# Arduino-UNO-SMD-Rev3e.net
KiCad netlist of a schematic drawn in EAGLE
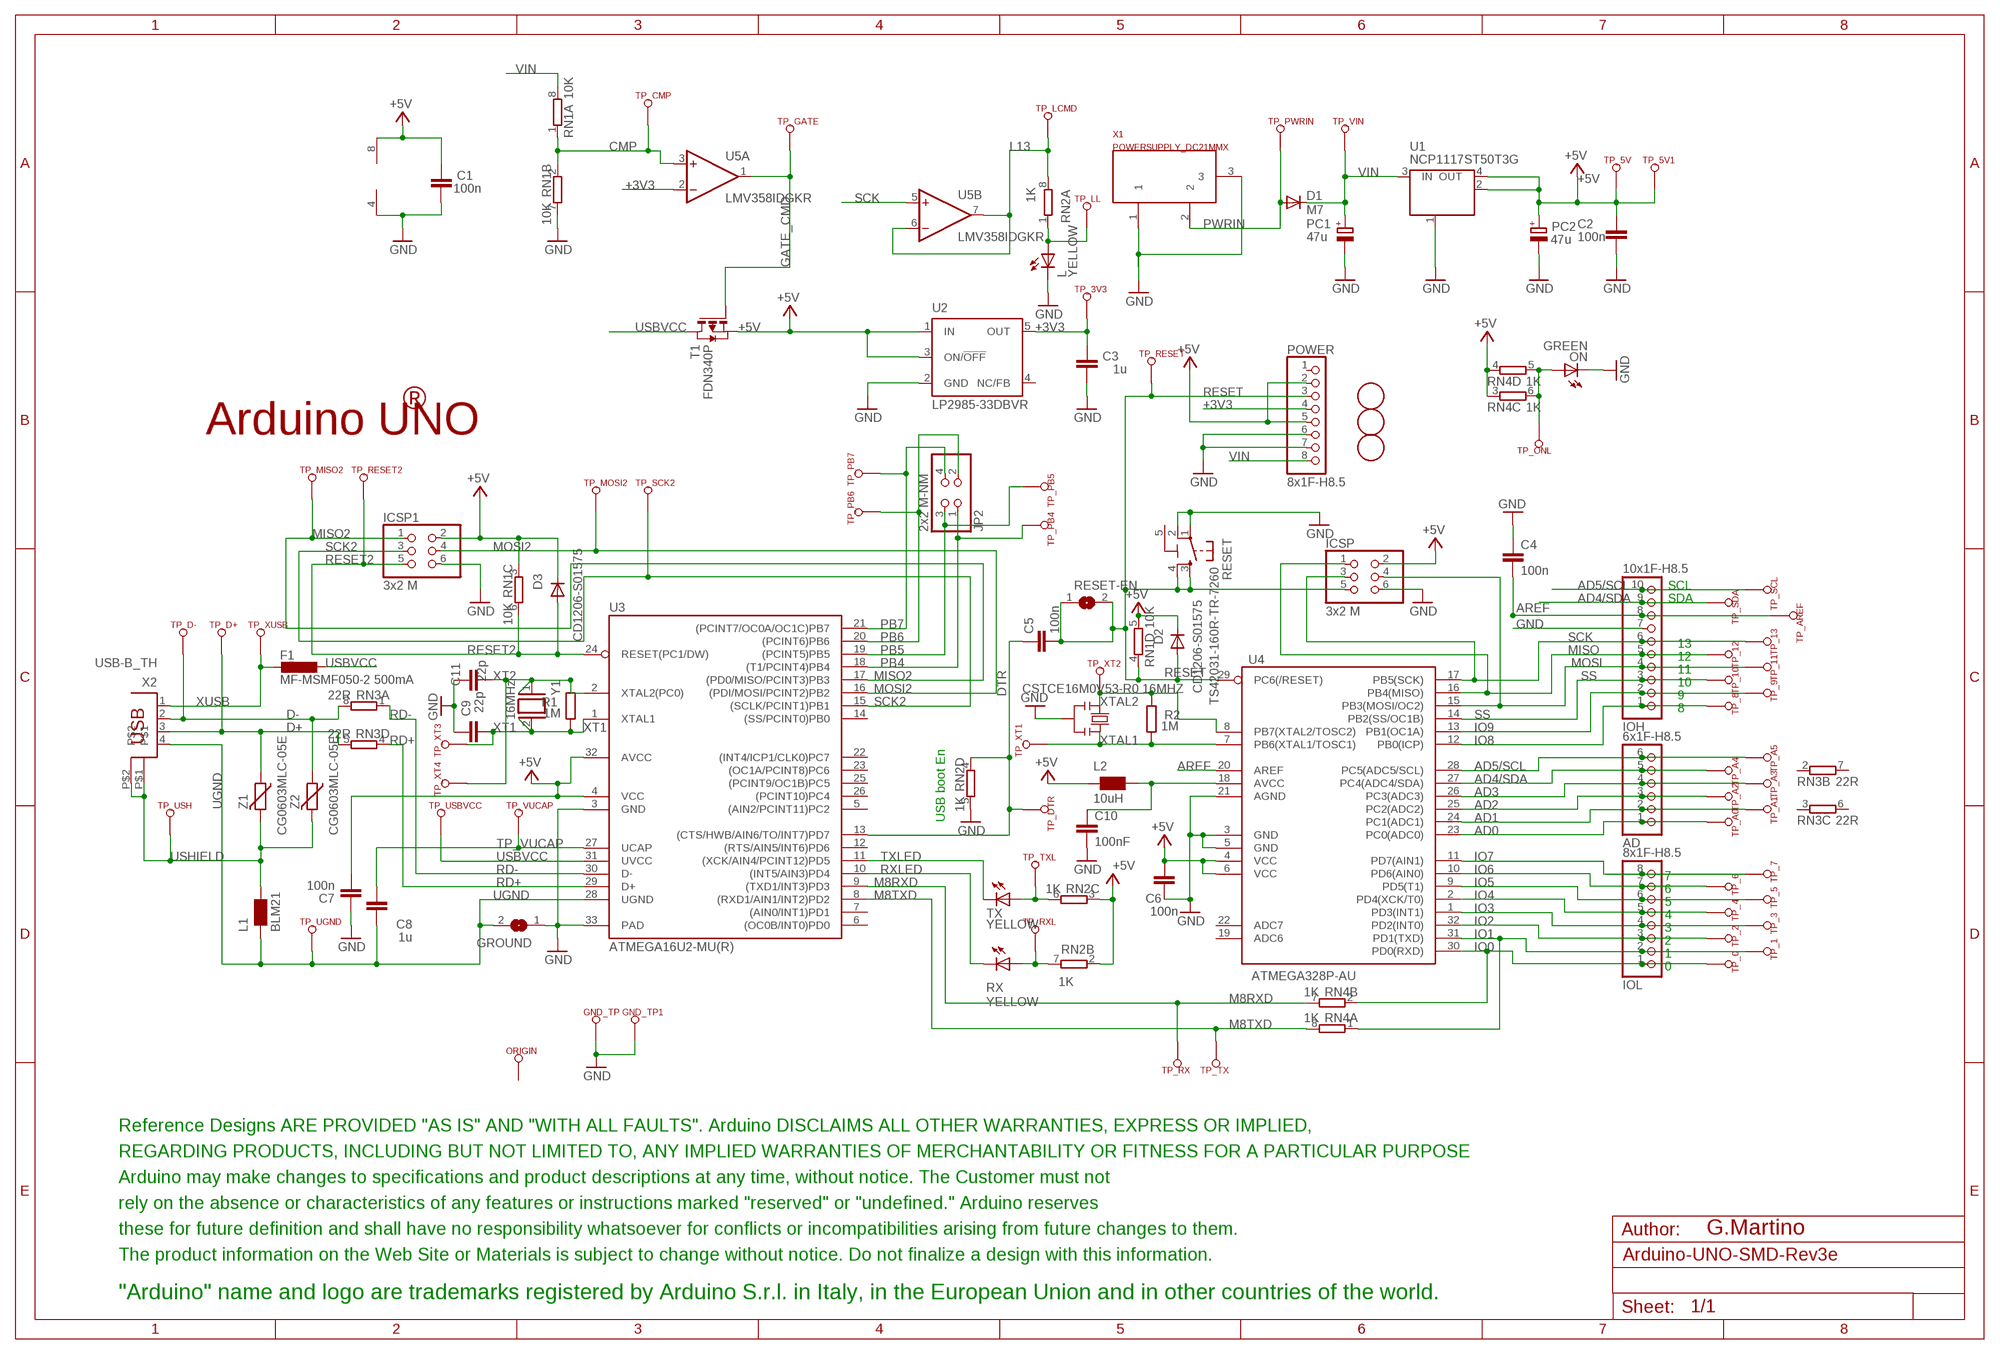
[diagram p0: schematic, sheet 1]

(export (version "E")
  (design (tool "Eeschema 10.0.6"))
  (components
    (comp (ref "AD")
      (value "6x1F-H8.5")
      (footprint "eagle-import:1X06")
      (libsource (lib "eagle-import") (part "PINHD-1X6"))
    )
    (comp (ref "C1")
      (value "100n")
      (footprint "eagle-import:C0603-ROUND")
      (libsource (lib "eagle-import") (part "C-EU0603-RND"))
    )
    (comp (ref "C2")
      (value "100n")
      (footprint "eagle-import:C0603-ROUND")
      (libsource (lib "eagle-import") (part "C-EU0603-RND"))
    )
    (comp (ref "C3")
      (value "1u")
      (footprint "eagle-import:C0603-ROUND")
      (libsource (lib "eagle-import") (part "C-EU0603-RND"))
    )
    (comp (ref "C4")
      (value "100n")
      (footprint "eagle-import:C0603-ROUND")
      (libsource (lib "eagle-import") (part "C-EU0603-RND"))
    )
    (comp (ref "C5")
      (value "100n")
      (footprint "eagle-import:C0603-ROUND")
      (libsource (lib "eagle-import") (part "C-EU0603-RND"))
    )
    (comp (ref "C6")
      (value "100n")
      (footprint "eagle-import:C0603-ROUND")
      (libsource (lib "eagle-import") (part "C-EU0603-RND"))
    )
    (comp (ref "C7")
      (value "100n")
      (footprint "eagle-import:C0603-ROUND")
      (libsource (lib "eagle-import") (part "C-EU0603-RND"))
    )
    (comp (ref "C8")
      (value "1u")
      (footprint "eagle-import:C0603-ROUND")
      (libsource (lib "eagle-import") (part "C-EU0603-RND"))
    )
    (comp (ref "C9")
      (value "22p")
      (footprint "eagle-import:C0603-ROUND")
      (libsource (lib "eagle-import") (part "C-EU0603-RND"))
    )
    (comp (ref "C10")
      (value "100nF")
      (footprint "eagle-import:C0603-ROUND")
      (fields (field (name "PART_NUMBER") "100nF_0603"))
      (libsource (lib "eagle-import") (part "0015_100NF_0603"))
    )
    (comp (ref "C11")
      (value "22p")
      (footprint "eagle-import:C0603-ROUND")
      (libsource (lib "eagle-import") (part "C-EU0603-RND"))
    )
    (comp (ref "D1")
      (value "M7")
      (footprint "eagle-import:SMB")
      (libsource (lib "eagle-import") (part "DIODE-SMB"))
    )
    (comp (ref "D2")
      (value "CD1206-S01575")
      (footprint "eagle-import:MINIMELF")
      (libsource (lib "eagle-import") (part "DIODE-MINIMELF"))
    )
    (comp (ref "D3")
      (value "CD1206-S01575")
      (footprint "eagle-import:MINIMELF")
      (libsource (lib "eagle-import") (part "DIODE-MINIMELF"))
    )
    (comp (ref "F1")
      (value "MF-MSMF050-2 500mA")
      (footprint "eagle-import:L1812")
      (libsource (lib "eagle-import") (part "L-EUL1812"))
    )
    (comp (ref "FD1")
      (value "FIDUCIALMOUNT")
      (footprint "eagle-import:FIDUCIA-MOUNT")
      (libsource (lib "eagle-import") (part "FIDUCIALMOUNT"))
    )
    (comp (ref "FD2")
      (value "FIDUCIALMOUNT")
      (footprint "eagle-import:FIDUCIA-MOUNT")
      (libsource (lib "eagle-import") (part "FIDUCIALMOUNT"))
    )
    (comp (ref "FD3")
      (value "FIDUCIALMOUNT")
      (footprint "eagle-import:FIDUCIA-MOUNT")
      (libsource (lib "eagle-import") (part "FIDUCIALMOUNT"))
    )
    (comp (ref "GND_TP")
      (value "TP_SP")
      (footprint "eagle-import:TP-SP")
      (libsource (lib "eagle-import") (part "TP_SP"))
    )
    (comp (ref "GND_TP1")
      (value "TP_SP")
      (footprint "eagle-import:TP-SP")
      (libsource (lib "eagle-import") (part "TP_SP"))
    )
    (comp (ref "GROUND")
      (value "SJ")
      (footprint "eagle-import:SJ")
      (libsource (lib "eagle-import") (part "SJ"))
    )
    (comp (ref "ICSP")
      (value "3x2 M")
      (footprint "eagle-import:2X03")
      (libsource (lib "eagle-import") (part "PINHD-2X3"))
    )
    (comp (ref "ICSP1")
      (value "3x2 M")
      (footprint "eagle-import:2X03")
      (libsource (lib "eagle-import") (part "PINHD-2X3"))
    )
    (comp (ref "IOH")
      (value "10x1F-H8.5")
      (footprint "eagle-import:1X10")
      (libsource (lib "eagle-import") (part "PINHD-1X10_ARD"))
    )
    (comp (ref "IOL")
      (value "8x1F-H8.5")
      (footprint "eagle-import:1X08")
      (libsource (lib "eagle-import") (part "PINHD-1X8"))
    )
    (comp (ref "JP2")
      (value "2x2 M-NM")
      (footprint "eagle-import:2X02")
      (libsource (lib "eagle-import") (part "PINHD-2X2"))
    )
    (comp (ref "L")
      (value "YELLOW")
      (footprint "eagle-import:CHIP-LED0805")
      (libsource (lib "eagle-import") (part "LEDCHIP-LED0805"))
    )
    (comp (ref "L1")
      (value "BLM21")
      (footprint "eagle-import:0805")
      (libsource (lib "eagle-import") (part "WE-CBF_0805"))
    )
    (comp (ref "L2")
      (value "10uH")
      (footprint "eagle-import:0805")
      (fields (field (name "PART_NUMBER") "CV201210-100K"))
      (libsource (lib "eagle-import") (part "0715_CV201210-100K"))
    )
    (comp (ref "ON")
      (value "GREEN")
      (footprint "eagle-import:CHIP-LED0805")
      (libsource (lib "eagle-import") (part "LEDCHIP-LED0805"))
    )
    (comp (ref "ORIGIN")
      (value "TP_SP")
      (footprint "eagle-import:TP-SP")
      (libsource (lib "eagle-import") (part "TP_SP"))
    )
    (comp (ref "PC1")
      (value "47u")
      (footprint "eagle-import:PANASONIC_D")
      (libsource (lib "eagle-import") (part "CPOL-EUD"))
    )
    (comp (ref "PC2")
      (value "47u")
      (footprint "eagle-import:PANASONIC_D")
      (libsource (lib "eagle-import") (part "CPOL-EUD"))
    )
    (comp (ref "POWER")
      (value "8x1F-H8.5")
      (footprint "eagle-import:1X08")
      (libsource (lib "eagle-import") (part "PINHD-1X8"))
    )
    (comp (ref "R1")
      (value "1M")
      (footprint "eagle-import:R0603-ROUND")
      (libsource (lib "eagle-import") (part "R-EU_R0603"))
    )
    (comp (ref "R2")
      (value "1M")
      (footprint "eagle-import:R0603-ROUND")
      (libsource (lib "eagle-import") (part "R-EU_R0603"))
    )
    (comp (ref "RESET")
      (value "TS42031-160R-TR-7260")
      (footprint "eagle-import:TS42")
      (libsource (lib "eagle-import") (part "TS42"))
    )
    (comp (ref "RESET-EN")
      (value "SJ")
      (footprint "eagle-import:SJ")
      (libsource (lib "eagle-import") (part "SJ"))
    )
    (comp (ref "RN1")
      (value "10K")
      (footprint "eagle-import:CAY16")
      (libsource (lib "eagle-import") (part "4R-NCAY16"))
    )
    (comp (ref "RN2")
      (value "1K")
      (footprint "eagle-import:CAY16")
      (libsource (lib "eagle-import") (part "4R-NCAY16"))
    )
    (comp (ref "RN3")
      (value "22R")
      (footprint "eagle-import:CAY16")
      (libsource (lib "eagle-import") (part "4R-NCAY16"))
    )
    (comp (ref "RN4")
      (value "1K")
      (footprint "eagle-import:CAY16")
      (libsource (lib "eagle-import") (part "4R-NCAY16"))
    )
    (comp (ref "RX")
      (value "YELLOW")
      (footprint "eagle-import:CHIP-LED0805")
      (libsource (lib "eagle-import") (part "LEDCHIP-LED0805"))
    )
    (comp (ref "T1")
      (value "FDN340P")
      (footprint "eagle-import:SOT-23")
      (libsource (lib "eagle-import") (part "PMOSSOT23"))
    )
    (comp (ref "TP_0")
      (value "TP_SP")
      (footprint "eagle-import:TP-SP")
      (libsource (lib "eagle-import") (part "TP_SP"))
    )
    (comp (ref "TP_1")
      (value "TP_SP")
      (footprint "eagle-import:TP-SP")
      (libsource (lib "eagle-import") (part "TP_SP"))
    )
    (comp (ref "TP_2")
      (value "TP_SP")
      (footprint "eagle-import:TP-SP")
      (libsource (lib "eagle-import") (part "TP_SP"))
    )
    (comp (ref "TP_3")
      (value "TP_SP")
      (footprint "eagle-import:TP-SP")
      (libsource (lib "eagle-import") (part "TP_SP"))
    )
    (comp (ref "TP_3V3")
      (value "TP_SP")
      (footprint "eagle-import:TP-SP")
      (libsource (lib "eagle-import") (part "TP_SP"))
    )
    (comp (ref "TP_4")
      (value "TP_SP")
      (footprint "eagle-import:TP-SP")
      (libsource (lib "eagle-import") (part "TP_SP"))
    )
    (comp (ref "TP_5")
      (value "TP_SP")
      (footprint "eagle-import:TP-SP")
      (libsource (lib "eagle-import") (part "TP_SP"))
    )
    (comp (ref "TP_5V")
      (value "TP_SP")
      (footprint "eagle-import:TP-SP")
      (libsource (lib "eagle-import") (part "TP_SP"))
    )
    (comp (ref "TP_5V1")
      (value "TP_SP")
      (footprint "eagle-import:TP-SP")
      (libsource (lib "eagle-import") (part "TP_SP"))
    )
    (comp (ref "TP_6")
      (value "TP_SP")
      (footprint "eagle-import:TP-SP")
      (libsource (lib "eagle-import") (part "TP_SP"))
    )
    (comp (ref "TP_7")
      (value "TP_SP")
      (footprint "eagle-import:TP-SP")
      (libsource (lib "eagle-import") (part "TP_SP"))
    )
    (comp (ref "TP_8")
      (value "TP_SP")
      (footprint "eagle-import:TP-SP")
      (libsource (lib "eagle-import") (part "TP_SP"))
    )
    (comp (ref "TP_9")
      (value "TP_SP")
      (footprint "eagle-import:TP-SP")
      (libsource (lib "eagle-import") (part "TP_SP"))
    )
    (comp (ref "TP_10")
      (value "TP_SP")
      (footprint "eagle-import:TP-SP")
      (libsource (lib "eagle-import") (part "TP_SP"))
    )
    (comp (ref "TP_11")
      (value "TP_SP")
      (footprint "eagle-import:TP-SP")
      (libsource (lib "eagle-import") (part "TP_SP"))
    )
    (comp (ref "TP_12")
      (value "TP_SP")
      (footprint "eagle-import:TP-SP")
      (libsource (lib "eagle-import") (part "TP_SP"))
    )
    (comp (ref "TP_13")
      (value "TP_SP")
      (footprint "eagle-import:TP-SP")
      (libsource (lib "eagle-import") (part "TP_SP"))
    )
    (comp (ref "TP_A0")
      (value "TP_SP")
      (footprint "eagle-import:TP-SP")
      (libsource (lib "eagle-import") (part "TP_SP"))
    )
    (comp (ref "TP_A1")
      (value "TP_SP")
      (footprint "eagle-import:TP-SP")
      (libsource (lib "eagle-import") (part "TP_SP"))
    )
    (comp (ref "TP_A2")
      (value "TP_SP")
      (footprint "eagle-import:TP-SP")
      (libsource (lib "eagle-import") (part "TP_SP"))
    )
    (comp (ref "TP_A3")
      (value "TP_SP")
      (footprint "eagle-import:TP-SP")
      (libsource (lib "eagle-import") (part "TP_SP"))
    )
    (comp (ref "TP_A4")
      (value "TP_SP")
      (footprint "eagle-import:TP-SP")
      (libsource (lib "eagle-import") (part "TP_SP"))
    )
    (comp (ref "TP_A5")
      (value "TP_SP")
      (footprint "eagle-import:TP-SP")
      (libsource (lib "eagle-import") (part "TP_SP"))
    )
    (comp (ref "TP_AREF")
      (value "TP_SP")
      (footprint "eagle-import:TP-SP")
      (libsource (lib "eagle-import") (part "TP_SP"))
    )
    (comp (ref "TP_CMP")
      (value "TP_SP")
      (footprint "eagle-import:TP-SP")
      (libsource (lib "eagle-import") (part "TP_SP"))
    )
    (comp (ref "TP_D+")
      (value "TP_SP")
      (footprint "eagle-import:TP-SP")
      (libsource (lib "eagle-import") (part "TP_SP"))
    )
    (comp (ref "TP_D-")
      (value "TP_SP")
      (footprint "eagle-import:TP-SP")
      (libsource (lib "eagle-import") (part "TP_SP"))
    )
    (comp (ref "TP_DTR")
      (value "TP_SP")
      (footprint "eagle-import:TP-SP")
      (libsource (lib "eagle-import") (part "TP_SP"))
    )
    (comp (ref "TP_GATE")
      (value "TP_SP")
      (footprint "eagle-import:TP-SP")
      (libsource (lib "eagle-import") (part "TP_SP"))
    )
    (comp (ref "TP_LCMD")
      (value "TP_SP")
      (footprint "eagle-import:TP-SP")
      (libsource (lib "eagle-import") (part "TP_SP"))
    )
    (comp (ref "TP_LL")
      (value "TP_SP")
      (footprint "eagle-import:TP-SP")
      (libsource (lib "eagle-import") (part "TP_SP"))
    )
    (comp (ref "TP_MISO2")
      (value "TP_SP")
      (footprint "eagle-import:TP-SP")
      (libsource (lib "eagle-import") (part "TP_SP"))
    )
    (comp (ref "TP_MOSI2")
      (value "TP_SP")
      (footprint "eagle-import:TP-SP")
      (libsource (lib "eagle-import") (part "TP_SP"))
    )
    (comp (ref "TP_ONL")
      (value "TP_SP")
      (footprint "eagle-import:TP-SP")
      (libsource (lib "eagle-import") (part "TP_SP"))
    )
    (comp (ref "TP_PB4")
      (value "TP_SP")
      (footprint "eagle-import:TP-SP")
      (libsource (lib "eagle-import") (part "TP_SP"))
    )
    (comp (ref "TP_PB5")
      (value "TP_SP")
      (footprint "eagle-import:TP-SP")
      (libsource (lib "eagle-import") (part "TP_SP"))
    )
    (comp (ref "TP_PB6")
      (value "TP_SP")
      (footprint "eagle-import:TP-SP")
      (libsource (lib "eagle-import") (part "TP_SP"))
    )
    (comp (ref "TP_PB7")
      (value "TP_SP")
      (footprint "eagle-import:TP-SP")
      (libsource (lib "eagle-import") (part "TP_SP"))
    )
    (comp (ref "TP_PWRIN")
      (value "TP_SP")
      (footprint "eagle-import:TP-SP")
      (libsource (lib "eagle-import") (part "TP_SP"))
    )
    (comp (ref "TP_RESET")
      (value "TP_SP")
      (footprint "eagle-import:TP-SP")
      (libsource (lib "eagle-import") (part "TP_SP"))
    )
    (comp (ref "TP_RESET2")
      (value "TP_SP")
      (footprint "eagle-import:TP-SP")
      (libsource (lib "eagle-import") (part "TP_SP"))
    )
    (comp (ref "TP_RX")
      (value "TP_SP")
      (footprint "eagle-import:TP-SP")
      (libsource (lib "eagle-import") (part "TP_SP"))
    )
    (comp (ref "TP_RXL")
      (value "TP_SP")
      (footprint "eagle-import:TP-SP")
      (libsource (lib "eagle-import") (part "TP_SP"))
    )
    (comp (ref "TP_SCK2")
      (value "TP_SP")
      (footprint "eagle-import:TP-SP")
      (libsource (lib "eagle-import") (part "TP_SP"))
    )
    (comp (ref "TP_SCL")
      (value "TP_SP")
      (footprint "eagle-import:TP-SP")
      (libsource (lib "eagle-import") (part "TP_SP"))
    )
    (comp (ref "TP_SDA")
      (value "TP_SP")
      (footprint "eagle-import:TP-SP")
      (libsource (lib "eagle-import") (part "TP_SP"))
    )
    (comp (ref "TP_TX")
      (value "TP_SP")
      (footprint "eagle-import:TP-SP")
      (libsource (lib "eagle-import") (part "TP_SP"))
    )
    (comp (ref "TP_TXL")
      (value "TP_SP")
      (footprint "eagle-import:TP-SP")
      (libsource (lib "eagle-import") (part "TP_SP"))
    )
    (comp (ref "TP_UGND")
      (value "TP_SP")
      (footprint "eagle-import:TP-SP")
      (libsource (lib "eagle-import") (part "TP_SP"))
    )
    (comp (ref "TP_USBVCC")
      (value "TP_SP")
      (footprint "eagle-import:TP-SP")
      (libsource (lib "eagle-import") (part "TP_SP"))
    )
    (comp (ref "TP_USH")
      (value "TP_SP")
      (footprint "eagle-import:TP-SP")
      (libsource (lib "eagle-import") (part "TP_SP"))
    )
    (comp (ref "TP_VIN")
      (value "TP_SP")
      (footprint "eagle-import:TP-SP")
      (libsource (lib "eagle-import") (part "TP_SP"))
    )
    (comp (ref "TP_VUCAP")
      (value "TP_SP")
      (footprint "eagle-import:TP-SP")
      (libsource (lib "eagle-import") (part "TP_SP"))
    )
    (comp (ref "TP_XT1")
      (value "TP_SP")
      (footprint "eagle-import:TP-SP")
      (libsource (lib "eagle-import") (part "TP_SP"))
    )
    (comp (ref "TP_XT2")
      (value "TP_SP")
      (footprint "eagle-import:TP-SP")
      (libsource (lib "eagle-import") (part "TP_SP"))
    )
    (comp (ref "TP_XT3")
      (value "TP_SP")
      (footprint "eagle-import:TP-SP")
      (libsource (lib "eagle-import") (part "TP_SP"))
    )
    (comp (ref "TP_XT4")
      (value "TP_SP")
      (footprint "eagle-import:TP-SP")
      (libsource (lib "eagle-import") (part "TP_SP"))
    )
    (comp (ref "TP_XUSB")
      (value "TP_SP")
      (footprint "eagle-import:TP-SP")
      (libsource (lib "eagle-import") (part "TP_SP"))
    )
    (comp (ref "TX")
      (value "YELLOW")
      (footprint "eagle-import:CHIP-LED0805")
      (libsource (lib "eagle-import") (part "LEDCHIP-LED0805"))
    )
    (comp (ref "U$2")
      (value "DISCLAIMER-SMALL")
      (footprint "eagle-import:DISCLAIMER")
      (libsource (lib "eagle-import") (part "DISCLAIMER-SMALL"))
    )
    (comp (ref "U1")
      (value "NCP1117ST50T3G")
      (footprint "eagle-import:SOT223")
      (libsource (lib "eagle-import") (part "MC33269ST-3.3T3"))
    )
    (comp (ref "U2")
      (value "LP2985-33DBVR")
      (footprint "eagle-import:SOT23-DBV")
      (libsource (lib "eagle-import") (part "LP2985-XXDBVR33"))
    )
    (comp (ref "U3")
      (value "ATMEGA16U2-MU(R)")
      (footprint "eagle-import:MLF32")
      (libsource (lib "eagle-import") (part "ATMEGA16U2-MU"))
    )
    (comp (ref "U4")
      (value "ATMEGA328P-AU")
      (footprint "eagle-import:MLF32")
      (libsource (lib "eagle-import") (part "ATMEGAXX8-MUR"))
    )
    (comp (ref "U5")
      (value "LMV358IDGKR")
      (footprint "eagle-import:MSOP08")
      (libsource (lib "eagle-import") (part "LMV358?MMX"))
    )
    (comp (ref "X1")
      (value "POWERSUPPLY_DC21MMX")
      (footprint "eagle-import:POWERSUPPLY_DC-21MM")
      (libsource (lib "eagle-import") (part "POWERSUPPLY_DC21MMX"))
    )
    (comp (ref "X2")
      (value "USB-B_TH")
      (footprint "eagle-import:PN61729")
      (libsource (lib "eagle-import") (part "PN61729"))
    )
    (comp (ref "Y1")
      (value "16MHz")
      (footprint "eagle-import:QS")
      (libsource (lib "eagle-import") (part "XTAL/S"))
    )
    (comp (ref "Y2")
      (value "CSTCE16M0V53-R0 16MHZ")
      (footprint "eagle-import:RESONATOR")
      (libsource (lib "eagle-import") (part "RESONATORMU"))
    )
    (comp (ref "Z1")
      (value "CG0603MLC-05E")
      (footprint "eagle-import:CT_CN0603")
      (libsource (lib "eagle-import") (part "VARISTORCN0603"))
    )
    (comp (ref "Z2")
      (value "CG0603MLC-05E")
      (footprint "eagle-import:CT_CN0603")
      (libsource (lib "eagle-import") (part "VARISTORCN0603"))
    )
  )
  (nets
    (net (code "1") (name "+5V") (class "Default")
      (node (ref "C1") (pin "2") (pinfunction "2_2") (pintype "passive"))
      (node (ref "C2") (pin "2") (pinfunction "2_2") (pintype "passive"))
      (node (ref "C6") (pin "2") (pinfunction "2_2") (pintype "passive"))
      (node (ref "C7") (pin "1") (pinfunction "1_1") (pintype "passive"))
      (node (ref "D2") (pin "C") (pinfunction "C_C") (pintype "passive"))
      (node (ref "D3") (pin "C") (pinfunction "C_C") (pintype "passive"))
      (node (ref "ICSP") (pin "2") (pinfunction "2_2") (pintype "passive"))
      (node (ref "ICSP1") (pin "2") (pinfunction "2_2") (pintype "passive"))
      (node (ref "L2") (pin "1") (pinfunction "1_1") (pintype "passive"))
      (node (ref "PC2") (pin "+") (pinfunction "+_+") (pintype "passive"))
      (node (ref "POWER") (pin "2") (pinfunction "2_2") (pintype "passive"))
      (node (ref "POWER") (pin "5") (pinfunction "5_5") (pintype "passive"))
      (node (ref "RN1") (pin "3") (pinfunction "1_3") (pintype "passive"))
      (node (ref "RN1") (pin "5") (pinfunction "2_5") (pintype "passive"))
      (node (ref "RN2") (pin "2") (pinfunction "1_2") (pintype "passive"))
      (node (ref "RN2") (pin "3") (pinfunction "1_3") (pintype "passive"))
      (node (ref "RN4") (pin "3") (pinfunction "1_3") (pintype "passive"))
      (node (ref "RN4") (pin "4") (pinfunction "1_4") (pintype "passive"))
      (node (ref "T1") (pin "2") (pinfunction "S_2") (pintype "passive"))
      (node (ref "TP_5V") (pin "X") (pinfunction "TESTP_X") (pintype "passive"))
      (node (ref "TP_5V1") (pin "X") (pinfunction "TESTP_X") (pintype "passive"))
      (node (ref "U1") (pin "2") (pinfunction "OUT_2") (pintype "passive"))
      (node (ref "U1") (pin "4") (pinfunction "OUT_4") (pintype "passive"))
      (node (ref "U2") (pin "1") (pinfunction "IN_1") (pintype "input"))
      (node (ref "U2") (pin "3") (pinfunction "ON/~{OFF}_3") (pintype "input"))
      (node (ref "U3") (pin "32") (pinfunction "AVCC_32") (pintype "power_in"))
      (node (ref "U3") (pin "4") (pinfunction "VCC_4") (pintype "power_in"))
      (node (ref "U4") (pin "4") (pinfunction "VCC_4") (pintype "bidirectional"))
      (node (ref "U4") (pin "6") (pinfunction "VCC_6") (pintype "bidirectional"))
      (node (ref "U5") (pin "8") (pinfunction "V+_8") (pintype "power_in"))
    )
    (net (code "2") (name "/+3V3") (class "Default")
      (node (ref "C3") (pin "2") (pinfunction "2_2") (pintype "passive"))
      (node (ref "POWER") (pin "4") (pinfunction "4_4") (pintype "passive"))
      (node (ref "TP_3V3") (pin "X") (pinfunction "TESTP_X") (pintype "passive"))
      (node (ref "U2") (pin "5") (pinfunction "OUT_5") (pintype "passive"))
      (node (ref "U5") (pin "2") (pinfunction "-IN_2") (pintype "input"))
    )
    (net (code "3") (name "/5-GND") (class "Default")
      (node (ref "RESET") (pin "5") (pinfunction "5-GND_5") (pintype "power_in"))
    )
    (net (code "4") (name "/AD0") (class "Default")
      (node (ref "AD") (pin "1") (pinfunction "1_1") (pintype "passive"))
      (node (ref "TP_A0") (pin "X") (pinfunction "TESTP_X") (pintype "passive"))
      (node (ref "U4") (pin "23") (pinfunction "PC0(ADC0)_23") (pintype "bidirectional"))
    )
    (net (code "5") (name "/AD1") (class "Default")
      (node (ref "AD") (pin "2") (pinfunction "2_2") (pintype "passive"))
      (node (ref "TP_A1") (pin "X") (pinfunction "TESTP_X") (pintype "passive"))
      (node (ref "U4") (pin "24") (pinfunction "PC1(ADC1)_24") (pintype "bidirectional"))
    )
    (net (code "6") (name "/AD2") (class "Default")
      (node (ref "AD") (pin "3") (pinfunction "3_3") (pintype "passive"))
      (node (ref "TP_A2") (pin "X") (pinfunction "TESTP_X") (pintype "passive"))
      (node (ref "U4") (pin "25") (pinfunction "PC2(ADC2)_25") (pintype "bidirectional"))
    )
    (net (code "7") (name "/AD3") (class "Default")
      (node (ref "AD") (pin "4") (pinfunction "4_4") (pintype "passive"))
      (node (ref "TP_A3") (pin "X") (pinfunction "TESTP_X") (pintype "passive"))
      (node (ref "U4") (pin "26") (pinfunction "PC3(ADC3)_26") (pintype "bidirectional"))
    )
    (net (code "8") (name "/AD4{slash}SDA") (class "Default")
      (node (ref "AD") (pin "5") (pinfunction "5_5") (pintype "passive"))
      (node (ref "IOH") (pin "9") (pinfunction "9_9") (pintype "passive"))
      (node (ref "TP_A4") (pin "X") (pinfunction "TESTP_X") (pintype "passive"))
      (node (ref "TP_SDA") (pin "X") (pinfunction "TESTP_X") (pintype "passive"))
      (node (ref "U4") (pin "27") (pinfunction "PC4(ADC4/SDA)_27") (pintype "bidirectional"))
    )
    (net (code "9") (name "/AD5{slash}SCL") (class "Default")
      (node (ref "AD") (pin "6") (pinfunction "6_6") (pintype "passive"))
      (node (ref "IOH") (pin "10") (pinfunction "10_10") (pintype "passive"))
      (node (ref "TP_A5") (pin "X") (pinfunction "TESTP_X") (pintype "passive"))
      (node (ref "TP_SCL") (pin "X") (pinfunction "TESTP_X") (pintype "passive"))
      (node (ref "U4") (pin "28") (pinfunction "PC5(ADC5/SCL)_28") (pintype "bidirectional"))
    )
    (net (code "10") (name "/AREF") (class "Default")
      (node (ref "C4") (pin "2") (pinfunction "2_2") (pintype "passive"))
      (node (ref "IOH") (pin "8") (pinfunction "8_8") (pintype "passive"))
      (node (ref "TP_AREF") (pin "X") (pinfunction "TESTP_X") (pintype "passive"))
      (node (ref "U4") (pin "20") (pinfunction "AREF_20") (pintype "bidirectional"))
    )
    (net (code "11") (name "/CMP") (class "Default")
      (node (ref "RN1") (pin "1") (pinfunction "1_1") (pintype "passive"))
      (node (ref "RN1") (pin "2") (pinfunction "1_2") (pintype "passive"))
      (node (ref "TP_CMP") (pin "X") (pinfunction "TESTP_X") (pintype "passive"))
      (node (ref "U5") (pin "3") (pinfunction "+IN_3") (pintype "input"))
    )
    (net (code "12") (name "/D+") (class "Default")
      (node (ref "RN3") (pin "5") (pinfunction "2_5") (pintype "passive"))
      (node (ref "TP_D+") (pin "X") (pinfunction "TESTP_X") (pintype "passive"))
      (node (ref "X2") (pin "3") (pinfunction "3_3") (pintype "bidirectional"))
      (node (ref "Z1") (pin "1") (pinfunction "1_1") (pintype "passive"))
    )
    (net (code "13") (name "/D-") (class "Default")
      (node (ref "RN3") (pin "8") (pinfunction "2_8") (pintype "passive"))
      (node (ref "TP_D-") (pin "X") (pinfunction "TESTP_X") (pintype "passive"))
      (node (ref "X2") (pin "2") (pinfunction "2_2") (pintype "bidirectional"))
      (node (ref "Z2") (pin "1") (pinfunction "1_1") (pintype "passive"))
    )
    (net (code "14") (name "/DTR") (class "Default")
      (node (ref "C5") (pin "1") (pinfunction "1_1") (pintype "passive"))
      (node (ref "RN2") (pin "4") (pinfunction "1_4") (pintype "passive"))
      (node (ref "TP_DTR") (pin "X") (pinfunction "TESTP_X") (pintype "passive"))
      (node (ref "U3") (pin "13") (pinfunction "(CTS/HWB/AIN6/TO/INT7)PD7_13") (pintype "bidirectional"))
    )
    (net (code "15") (name "/GATE_CMD") (class "Default")
      (node (ref "T1") (pin "3") (pinfunction "G_3") (pintype "passive"))
      (node (ref "TP_GATE") (pin "X") (pinfunction "TESTP_X") (pintype "passive"))
      (node (ref "U5") (pin "1") (pinfunction "OUT_1") (pintype "output"))
    )
    (net (code "16") (name "/IO0") (class "Default")
      (node (ref "IOL") (pin "1") (pinfunction "1_1") (pintype "passive"))
      (node (ref "RN4") (pin "2") (pinfunction "1_2") (pintype "passive"))
      (node (ref "TP_0") (pin "X") (pinfunction "TESTP_X") (pintype "passive"))
      (node (ref "U4") (pin "30") (pinfunction "PD0(RXD)_30") (pintype "bidirectional"))
    )
    (net (code "17") (name "/IO1") (class "Default")
      (node (ref "IOL") (pin "2") (pinfunction "2_2") (pintype "passive"))
      (node (ref "RN4") (pin "1") (pinfunction "1_1") (pintype "passive"))
      (node (ref "TP_1") (pin "X") (pinfunction "TESTP_X") (pintype "passive"))
      (node (ref "U4") (pin "31") (pinfunction "PD1(TXD)_31") (pintype "bidirectional"))
    )
    (net (code "18") (name "/IO2") (class "Default")
      (node (ref "IOL") (pin "3") (pinfunction "3_3") (pintype "passive"))
      (node (ref "TP_2") (pin "X") (pinfunction "TESTP_X") (pintype "passive"))
      (node (ref "U4") (pin "32") (pinfunction "PD2(INT0)_32") (pintype "bidirectional"))
    )
    (net (code "19") (name "/IO3") (class "Default")
      (node (ref "IOL") (pin "4") (pinfunction "4_4") (pintype "passive"))
      (node (ref "TP_3") (pin "X") (pinfunction "TESTP_X") (pintype "passive"))
      (node (ref "U4") (pin "1") (pinfunction "PD3(INT1)_1") (pintype "bidirectional"))
    )
    (net (code "20") (name "/IO4") (class "Default")
      (node (ref "IOL") (pin "5") (pinfunction "5_5") (pintype "passive"))
      (node (ref "TP_4") (pin "X") (pinfunction "TESTP_X") (pintype "passive"))
      (node (ref "U4") (pin "2") (pinfunction "PD4(XCK/T0)_2") (pintype "bidirectional"))
    )
    (net (code "21") (name "/IO5") (class "Default")
      (node (ref "IOL") (pin "6") (pinfunction "6_6") (pintype "passive"))
      (node (ref "TP_5") (pin "X") (pinfunction "TESTP_X") (pintype "passive"))
      (node (ref "U4") (pin "9") (pinfunction "PD5(T1)_9") (pintype "bidirectional"))
    )
    (net (code "22") (name "/IO6") (class "Default")
      (node (ref "IOL") (pin "7") (pinfunction "7_7") (pintype "passive"))
      (node (ref "TP_6") (pin "X") (pinfunction "TESTP_X") (pintype "passive"))
      (node (ref "U4") (pin "10") (pinfunction "PD6(AIN0)_10") (pintype "bidirectional"))
    )
    (net (code "23") (name "/IO7") (class "Default")
      (node (ref "IOL") (pin "8") (pinfunction "8_8") (pintype "passive"))
      (node (ref "TP_7") (pin "X") (pinfunction "TESTP_X") (pintype "passive"))
      (node (ref "U4") (pin "11") (pinfunction "PD7(AIN1)_11") (pintype "bidirectional"))
    )
    (net (code "24") (name "/IO8") (class "Default")
      (node (ref "IOH") (pin "1") (pinfunction "1_1") (pintype "passive"))
      (node (ref "TP_8") (pin "X") (pinfunction "TESTP_X") (pintype "passive"))
      (node (ref "U4") (pin "12") (pinfunction "PB0(ICP)_12") (pintype "bidirectional"))
    )
    (net (code "25") (name "/IO9") (class "Default")
      (node (ref "IOH") (pin "2") (pinfunction "2_2") (pintype "passive"))
      (node (ref "TP_9") (pin "X") (pinfunction "TESTP_X") (pintype "passive"))
      (node (ref "U4") (pin "13") (pinfunction "PB1(OC1A)_13") (pintype "bidirectional"))
    )
    (net (code "26") (name "/L13") (class "Default")
      (node (ref "RN2") (pin "8") (pinfunction "2_8") (pintype "passive"))
      (node (ref "TP_LCMD") (pin "X") (pinfunction "TESTP_X") (pintype "passive"))
      (node (ref "U5") (pin "6") (pinfunction "-IN_6") (pintype "input"))
      (node (ref "U5") (pin "7") (pinfunction "OUT_7") (pintype "output"))
    )
    (net (code "27") (name "/M8RXD") (class "Default")
      (node (ref "RN4") (pin "7") (pinfunction "2_7") (pintype "passive"))
      (node (ref "TP_RX") (pin "X") (pinfunction "TESTP_X") (pintype "passive"))
      (node (ref "U3") (pin "9") (pinfunction "(TXD1/INT3)PD3_9") (pintype "bidirectional"))
    )
    (net (code "28") (name "/M8TXD") (class "Default")
      (node (ref "RN4") (pin "8") (pinfunction "2_8") (pintype "passive"))
      (node (ref "TP_TX") (pin "X") (pinfunction "TESTP_X") (pintype "passive"))
      (node (ref "U3") (pin "8") (pinfunction "(RXD1/AIN1/INT2)PD2_8") (pintype "bidirectional"))
    )
    (net (code "29") (name "/MISO") (class "Default")
      (node (ref "ICSP") (pin "1") (pinfunction "1_1") (pintype "passive"))
      (node (ref "IOH") (pin "5") (pinfunction "5_5") (pintype "passive"))
      (node (ref "TP_12") (pin "X") (pinfunction "TESTP_X") (pintype "passive"))
      (node (ref "U4") (pin "16") (pinfunction "PB4(MISO)_16") (pintype "bidirectional"))
    )
    (net (code "30") (name "/MISO2") (class "Default")
      (node (ref "ICSP1") (pin "1") (pinfunction "1_1") (pintype "passive"))
      (node (ref "TP_MISO2") (pin "X") (pinfunction "TESTP_X") (pintype "passive"))
      (node (ref "U3") (pin "17") (pinfunction "(PD0/MISO/PCINT3)PB3_17") (pintype "bidirectional"))
    )
    (net (code "31") (name "/MOSI") (class "Default")
      (node (ref "ICSP") (pin "4") (pinfunction "4_4") (pintype "passive"))
      (node (ref "IOH") (pin "4") (pinfunction "4_4") (pintype "passive"))
      (node (ref "TP_11") (pin "X") (pinfunction "TESTP_X") (pintype "passive"))
      (node (ref "U4") (pin "15") (pinfunction "PB3(MOSI/OC2)_15") (pintype "bidirectional"))
    )
    (net (code "32") (name "/MOSI2") (class "Default")
      (node (ref "ICSP1") (pin "4") (pinfunction "4_4") (pintype "passive"))
      (node (ref "TP_MOSI2") (pin "X") (pinfunction "TESTP_X") (pintype "passive"))
      (node (ref "U3") (pin "16") (pinfunction "(PDI/MOSI/PCINT2)PB2_16") (pintype "bidirectional"))
    )
    (net (code "33") (name "/PB4") (class "Default")
      (node (ref "JP2") (pin "1") (pinfunction "1_1") (pintype "passive"))
      (node (ref "TP_PB4") (pin "X") (pinfunction "TESTP_X") (pintype "passive"))
      (node (ref "U3") (pin "18") (pinfunction "(T1/PCINT4)PB4_18") (pintype "bidirectional"))
    )
    (net (code "34") (name "/PB5") (class "Default")
      (node (ref "JP2") (pin "3") (pinfunction "3_3") (pintype "passive"))
      (node (ref "TP_PB5") (pin "X") (pinfunction "TESTP_X") (pintype "passive"))
      (node (ref "U3") (pin "19") (pinfunction "(PCINT5)PB5_19") (pintype "bidirectional"))
    )
    (net (code "35") (name "/PB6") (class "Default")
      (node (ref "JP2") (pin "2") (pinfunction "2_2") (pintype "passive"))
      (node (ref "TP_PB6") (pin "X") (pinfunction "TESTP_X") (pintype "passive"))
      (node (ref "U3") (pin "20") (pinfunction "(PCINT6)PB6_20") (pintype "bidirectional"))
    )
    (net (code "36") (name "/PB7") (class "Default")
      (node (ref "JP2") (pin "4") (pinfunction "4_4") (pintype "passive"))
      (node (ref "TP_PB7") (pin "X") (pinfunction "TESTP_X") (pintype "passive"))
      (node (ref "U3") (pin "21") (pinfunction "(PCINT7/OC0A/OC1C)PB7_21") (pintype "bidirectional"))
    )
    (net (code "37") (name "/PWRIN") (class "Default")
      (node (ref "D1") (pin "A") (pinfunction "A_A") (pintype "passive"))
      (node (ref "TP_PWRIN") (pin "X") (pinfunction "TESTP_X") (pintype "passive"))
      (node (ref "X1") (pin "2") (pinfunction "2_2") (pintype "power_in"))
    )
    (net (code "38") (name "/RD+") (class "Default")
      (node (ref "RN3") (pin "4") (pinfunction "1_4") (pintype "passive"))
      (node (ref "U3") (pin "29") (pinfunction "D+_29") (pintype "bidirectional"))
    )
    (net (code "39") (name "/RD-") (class "Default")
      (node (ref "RN3") (pin "1") (pinfunction "1_1") (pintype "passive"))
      (node (ref "U3") (pin "30") (pinfunction "D-_30") (pintype "bidirectional"))
    )
    (net (code "40") (name "/RESET") (class "Default")
      (node (ref "C5") (pin "2") (pinfunction "2_2") (pintype "passive"))
      (node (ref "D2") (pin "A") (pinfunction "A_A") (pintype "passive"))
      (node (ref "ICSP") (pin "5") (pinfunction "5_5") (pintype "passive"))
      (node (ref "POWER") (pin "3") (pinfunction "3_3") (pintype "passive"))
      (node (ref "RESET") (pin "3") (pinfunction "3_3") (pintype "passive"))
      (node (ref "RESET") (pin "4") (pinfunction "4_4") (pintype "passive"))
      (node (ref "RESET-EN") (pin "1") (pinfunction "1_1") (pintype "passive"))
      (node (ref "RESET-EN") (pin "2") (pinfunction "2_2") (pintype "passive"))
      (node (ref "RN1") (pin "4") (pinfunction "1_4") (pintype "passive"))
      (node (ref "TP_RESET") (pin "X") (pinfunction "TESTP_X") (pintype "passive"))
      (node (ref "U4") (pin "29") (pinfunction "PC6(/RESET)_29") (pintype "bidirectional"))
    )
    (net (code "41") (name "/RESET2") (class "Default")
      (node (ref "D3") (pin "A") (pinfunction "A_A") (pintype "passive"))
      (node (ref "ICSP1") (pin "5") (pinfunction "5_5") (pintype "passive"))
      (node (ref "RN1") (pin "6") (pinfunction "2_6") (pintype "passive"))
      (node (ref "TP_RESET2") (pin "X") (pinfunction "TESTP_X") (pintype "passive"))
      (node (ref "U3") (pin "24") (pinfunction "RESET(PC1/DW)_24") (pintype "input"))
    )
    (net (code "42") (name "/RXLED") (class "Default")
      (node (ref "RX") (pin "C") (pinfunction "C_C") (pintype "passive"))
      (node (ref "U3") (pin "10") (pinfunction "(INT5/AIN3)PD4_10") (pintype "bidirectional"))
    )
    (net (code "43") (name "/SCK") (class "Default")
      (node (ref "ICSP") (pin "3") (pinfunction "3_3") (pintype "passive"))
      (node (ref "IOH") (pin "6") (pinfunction "6_6") (pintype "passive"))
      (node (ref "TP_13") (pin "X") (pinfunction "TESTP_X") (pintype "passive"))
      (node (ref "U4") (pin "17") (pinfunction "PB5(SCK)_17") (pintype "bidirectional"))
      (node (ref "U5") (pin "5") (pinfunction "+IN_5") (pintype "input"))
    )
    (net (code "44") (name "/SCK2") (class "Default")
      (node (ref "ICSP1") (pin "3") (pinfunction "3_3") (pintype "passive"))
      (node (ref "TP_SCK2") (pin "X") (pinfunction "TESTP_X") (pintype "passive"))
      (node (ref "U3") (pin "15") (pinfunction "(SCLK/PCINT1)PB1_15") (pintype "bidirectional"))
    )
    (net (code "45") (name "/SS") (class "Default")
      (node (ref "IOH") (pin "3") (pinfunction "3_3") (pintype "passive"))
      (node (ref "TP_10") (pin "X") (pinfunction "TESTP_X") (pintype "passive"))
      (node (ref "U4") (pin "14") (pinfunction "PB2(SS/OC1B)_14") (pintype "bidirectional"))
    )
    (net (code "46") (name "/TP_VUCAP") (class "Default")
      (node (ref "C8") (pin "1") (pinfunction "1_1") (pintype "passive"))
      (node (ref "TP_VUCAP") (pin "X") (pinfunction "TESTP_X") (pintype "passive"))
      (node (ref "U3") (pin "27") (pinfunction "UCAP_27") (pintype "passive"))
    )
    (net (code "47") (name "/TXLED") (class "Default")
      (node (ref "TX") (pin "C") (pinfunction "C_C") (pintype "passive"))
      (node (ref "U3") (pin "11") (pinfunction "(XCK/AIN4/PCINT12)PD5_11") (pintype "bidirectional"))
    )
    (net (code "48") (name "/UGND") (class "Default")
      (node (ref "C8") (pin "2") (pinfunction "2_2") (pintype "passive"))
      (node (ref "GROUND") (pin "2") (pinfunction "2_2") (pintype "passive"))
      (node (ref "L1") (pin "1") (pinfunction "1_1") (pintype "passive"))
      (node (ref "TP_UGND") (pin "X") (pinfunction "TESTP_X") (pintype "passive"))
      (node (ref "U3") (pin "28") (pinfunction "UGND_28") (pintype "power_in"))
      (node (ref "X2") (pin "4") (pinfunction "4_4") (pintype "bidirectional"))
    )
    (net (code "49") (name "/USBVCC") (class "Default")
      (node (ref "F1") (pin "1") (pinfunction "1_1") (pintype "passive"))
      (node (ref "T1") (pin "1") (pinfunction "D_1") (pintype "passive"))
      (node (ref "TP_USBVCC") (pin "X") (pinfunction "TESTP_X") (pintype "passive"))
      (node (ref "U3") (pin "31") (pinfunction "UVCC_31") (pintype "power_in"))
    )
    (net (code "50") (name "/USHIELD") (class "Default")
      (node (ref "L1") (pin "2") (pinfunction "2_2") (pintype "passive"))
      (node (ref "TP_USH") (pin "X") (pinfunction "TESTP_X") (pintype "passive"))
      (node (ref "X2") (pin "P$1") (pinfunction "P$1_P$1") (pintype "bidirectional"))
      (node (ref "X2") (pin "P$2") (pinfunction "P$2_P$2") (pintype "bidirectional"))
      (node (ref "Z1") (pin "2") (pinfunction "2_2") (pintype "passive"))
      (node (ref "Z2") (pin "2") (pinfunction "2_2") (pintype "passive"))
    )
    (net (code "51") (name "/VIN") (class "Default")
      (node (ref "D1") (pin "C") (pinfunction "C_C") (pintype "passive"))
      (node (ref "PC1") (pin "+") (pinfunction "+_+") (pintype "passive"))
      (node (ref "POWER") (pin "8") (pinfunction "8_8") (pintype "passive"))
      (node (ref "RN1") (pin "8") (pinfunction "2_8") (pintype "passive"))
      (node (ref "TP_VIN") (pin "X") (pinfunction "TESTP_X") (pintype "passive"))
      (node (ref "U1") (pin "3") (pinfunction "IN_3") (pintype "input"))
    )
    (net (code "52") (name "/XT1") (class "Default")
      (node (ref "C9") (pin "1") (pinfunction "1_1") (pintype "passive"))
      (node (ref "R1") (pin "1") (pinfunction "1_1") (pintype "passive"))
      (node (ref "TP_XT3") (pin "X") (pinfunction "TESTP_X") (pintype "passive"))
      (node (ref "U3") (pin "1") (pinfunction "XTAL1_1") (pintype "bidirectional"))
      (node (ref "Y1") (pin "2") (pinfunction "2_2") (pintype "passive"))
    )
    (net (code "53") (name "/XT2") (class "Default")
      (node (ref "C11") (pin "1") (pinfunction "1_1") (pintype "passive"))
      (node (ref "R1") (pin "2") (pinfunction "2_2") (pintype "passive"))
      (node (ref "TP_XT4") (pin "X") (pinfunction "TESTP_X") (pintype "passive"))
      (node (ref "U3") (pin "2") (pinfunction "XTAL2(PC0)_2") (pintype "bidirectional"))
      (node (ref "Y1") (pin "1") (pinfunction "1_1") (pintype "passive"))
    )
    (net (code "54") (name "/XTAL1") (class "Default")
      (node (ref "R2") (pin "1") (pinfunction "1_1") (pintype "passive"))
      (node (ref "TP_XT1") (pin "X") (pinfunction "TESTP_X") (pintype "passive"))
      (node (ref "U4") (pin "7") (pinfunction "PB6(XTAL1/TOSC1)_7") (pintype "bidirectional"))
      (node (ref "Y2") (pin "3") (pinfunction "3_3") (pintype "passive"))
    )
    (net (code "55") (name "/XTAL2") (class "Default")
      (node (ref "R2") (pin "2") (pinfunction "2_2") (pintype "passive"))
      (node (ref "TP_XT2") (pin "X") (pinfunction "TESTP_X") (pintype "passive"))
      (node (ref "U4") (pin "8") (pinfunction "PB7(XTAL2/TOSC2)_8") (pintype "bidirectional"))
      (node (ref "Y2") (pin "1") (pinfunction "1_1") (pintype "passive"))
    )
    (net (code "56") (name "/XUSB") (class "Default")
      (node (ref "F1") (pin "2") (pinfunction "2_2") (pintype "passive"))
      (node (ref "TP_XUSB") (pin "X") (pinfunction "TESTP_X") (pintype "passive"))
      (node (ref "X2") (pin "1") (pinfunction "1_1") (pintype "bidirectional"))
    )
    (net (code "57") (name "GND") (class "Default")
      (node (ref "C1") (pin "1") (pinfunction "1_1") (pintype "passive"))
      (node (ref "C10") (pin "2") (pinfunction "2_2") (pintype "passive"))
      (node (ref "C11") (pin "2") (pinfunction "2_2") (pintype "passive"))
      (node (ref "C2") (pin "1") (pinfunction "1_1") (pintype "passive"))
      (node (ref "C3") (pin "1") (pinfunction "1_1") (pintype "passive"))
      (node (ref "C4") (pin "1") (pinfunction "1_1") (pintype "passive"))
      (node (ref "C6") (pin "1") (pinfunction "1_1") (pintype "passive"))
      (node (ref "C7") (pin "2") (pinfunction "2_2") (pintype "passive"))
      (node (ref "C9") (pin "2") (pinfunction "2_2") (pintype "passive"))
      (node (ref "GND_TP") (pin "X") (pinfunction "TESTP_X") (pintype "passive"))
      (node (ref "GND_TP1") (pin "X") (pinfunction "TESTP_X") (pintype "passive"))
      (node (ref "GROUND") (pin "1") (pinfunction "1_1") (pintype "passive"))
      (node (ref "ICSP") (pin "6") (pinfunction "6_6") (pintype "passive"))
      (node (ref "ICSP1") (pin "6") (pinfunction "6_6") (pintype "passive"))
      (node (ref "IOH") (pin "7") (pinfunction "7_7") (pintype "passive"))
      (node (ref "L") (pin "C") (pinfunction "C_C") (pintype "passive"))
      (node (ref "ON") (pin "C") (pinfunction "C_C") (pintype "passive"))
      (node (ref "PC1") (pin "-") (pinfunction "-_-") (pintype "passive"))
      (node (ref "PC2") (pin "-") (pinfunction "-_-") (pintype "passive"))
      (node (ref "POWER") (pin "6") (pinfunction "6_6") (pintype "passive"))
      (node (ref "POWER") (pin "7") (pinfunction "7_7") (pintype "passive"))
      (node (ref "RESET") (pin "1") (pinfunction "1_1") (pintype "passive"))
      (node (ref "RESET") (pin "2") (pinfunction "2_2") (pintype "passive"))
      (node (ref "RN1") (pin "7") (pinfunction "2_7") (pintype "passive"))
      (node (ref "RN2") (pin "5") (pinfunction "2_5") (pintype "passive"))
      (node (ref "U1") (pin "1") (pinfunction "GND/ADJ_1") (pintype "input"))
      (node (ref "U2") (pin "2") (pinfunction "GND_2") (pintype "power_in"))
      (node (ref "U3") (pin "3") (pinfunction "GND_3") (pintype "power_in"))
      (node (ref "U3") (pin "33") (pinfunction "PAD_33") (pintype "power_in"))
      (node (ref "U4") (pin "21") (pinfunction "AGND_21") (pintype "bidirectional"))
      (node (ref "U4") (pin "3") (pinfunction "GND_3") (pintype "bidirectional"))
      (node (ref "U4") (pin "5") (pinfunction "GND_5") (pintype "bidirectional"))
      (node (ref "U5") (pin "4") (pinfunction "V-_4") (pintype "power_in"))
      (node (ref "X1") (pin "1") (pinfunction "1_1") (pintype "power_in"))
      (node (ref "X1") (pin "3") (pinfunction "3_3") (pintype "power_in"))
      (node (ref "Y2") (pin "2") (pinfunction "2_2") (pintype "passive"))
    )
    (net (code "58") (name "Net-(RN2B-2)") (class "Default")
      (node (ref "RN2") (pin "7") (pinfunction "2_7") (pintype "passive"))
      (node (ref "RX") (pin "A") (pinfunction "A_A") (pintype "passive"))
      (node (ref "TP_RXL") (pin "X") (pinfunction "TESTP_X") (pintype "passive"))
    )
    (net (code "59") (name "Net-(RN2C-2)") (class "Default")
      (node (ref "RN2") (pin "6") (pinfunction "2_6") (pintype "passive"))
      (node (ref "TP_TXL") (pin "X") (pinfunction "TESTP_X") (pintype "passive"))
      (node (ref "TX") (pin "A") (pinfunction "A_A") (pintype "passive"))
    )
    (net (code "60") (name "Net-(RN4C-2)") (class "Default")
      (node (ref "ON") (pin "A") (pinfunction "A_A") (pintype "passive"))
      (node (ref "RN4") (pin "5") (pinfunction "2_5") (pintype "passive"))
      (node (ref "RN4") (pin "6") (pinfunction "2_6") (pintype "passive"))
      (node (ref "TP_ONL") (pin "X") (pinfunction "TESTP_X") (pintype "passive"))
    )
    (net (code "61") (name "Net-(TP_LL-TESTP)") (class "Default")
      (node (ref "L") (pin "A") (pinfunction "A_A") (pintype "passive"))
      (node (ref "RN2") (pin "1") (pinfunction "1_1") (pintype "passive"))
      (node (ref "TP_LL") (pin "X") (pinfunction "TESTP_X") (pintype "passive"))
    )
    (net (code "62") (name "Net-(U4-AVCC)") (class "Default")
      (node (ref "C10") (pin "1") (pinfunction "1_1") (pintype "passive"))
      (node (ref "L2") (pin "2") (pinfunction "2_2") (pintype "passive"))
      (node (ref "U4") (pin "18") (pinfunction "AVCC_18") (pintype "bidirectional"))
    )
    (net (code "63") (name "unconnected-(ORIGIN-TESTP-PadX)") (class "Default")
      (node (ref "ORIGIN") (pin "X") (pinfunction "TESTP_X") (pintype "passive"))
    )
    (net (code "64") (name "unconnected-(POWER-Pad1)") (class "Default")
      (node (ref "POWER") (pin "1") (pinfunction "1_1") (pintype "passive"))
    )
    (net (code "65") (name "unconnected-(RN3B-1-Pad2)") (class "Default")
      (node (ref "RN3") (pin "2") (pinfunction "1_2") (pintype "passive"))
    )
    (net (code "66") (name "unconnected-(RN3B-2-Pad7)") (class "Default")
      (node (ref "RN3") (pin "7") (pinfunction "2_7") (pintype "passive"))
    )
    (net (code "67") (name "unconnected-(RN3C-1-Pad3)") (class "Default")
      (node (ref "RN3") (pin "3") (pinfunction "1_3") (pintype "passive"))
    )
    (net (code "68") (name "unconnected-(RN3C-2-Pad6)") (class "Default")
      (node (ref "RN3") (pin "6") (pinfunction "2_6") (pintype "passive"))
    )
    (net (code "69") (name "unconnected-(U2-NC{slash}FB-Pad4)") (class "Default")
      (node (ref "U2") (pin "4") (pinfunction "NC/FB_4") (pintype "passive"))
    )
    (net (code "70") (name "unconnected-(U3-(AIN0{slash}INT1)PD1-Pad7)") (class "Default")
      (node (ref "U3") (pin "7") (pinfunction "(AIN0/INT1)PD1_7") (pintype "bidirectional"))
    )
    (net (code "71") (name "unconnected-(U3-(AIN2{slash}PCINT11)PC2-Pad5)") (class "Default")
      (node (ref "U3") (pin "5") (pinfunction "(AIN2/PCINT11)PC2_5") (pintype "bidirectional"))
    )
    (net (code "72") (name "unconnected-(U3-(INT4{slash}ICP1{slash}CLK0)PC7-Pad22)") (class "Default")
      (node (ref "U3") (pin "22") (pinfunction "(INT4/ICP1/CLK0)PC7_22") (pintype "bidirectional"))
    )
    (net (code "73") (name "unconnected-(U3-(OC0B{slash}INT0)PD0-Pad6)") (class "Default")
      (node (ref "U3") (pin "6") (pinfunction "(OC0B/INT0)PD0_6") (pintype "bidirectional"))
    )
    (net (code "74") (name "unconnected-(U3-(OC1A{slash}PCINT8)PC6-Pad23)") (class "Default")
      (node (ref "U3") (pin "23") (pinfunction "(OC1A/PCINT8)PC6_23") (pintype "bidirectional"))
    )
    (net (code "75") (name "unconnected-(U3-(PCINT9{slash}OC1B)PC5-Pad25)") (class "Default")
      (node (ref "U3") (pin "25") (pinfunction "(PCINT9/OC1B)PC5_25") (pintype "bidirectional"))
    )
    (net (code "76") (name "unconnected-(U3-(PCINT10)PC4-Pad26)") (class "Default")
      (node (ref "U3") (pin "26") (pinfunction "(PCINT10)PC4_26") (pintype "bidirectional"))
    )
    (net (code "77") (name "unconnected-(U3-(RTS{slash}AIN5{slash}INT6)PD6-Pad12)") (class "Default")
      (node (ref "U3") (pin "12") (pinfunction "(RTS/AIN5/INT6)PD6_12") (pintype "bidirectional"))
    )
    (net (code "78") (name "unconnected-(U3-(SS{slash}PCINT0)PB0-Pad14)") (class "Default")
      (node (ref "U3") (pin "14") (pinfunction "(SS/PCINT0)PB0_14") (pintype "bidirectional"))
    )
    (net (code "79") (name "unconnected-(U4-ADC6-Pad19)") (class "Default")
      (node (ref "U4") (pin "19") (pinfunction "ADC6_19") (pintype "bidirectional"))
    )
    (net (code "80") (name "unconnected-(U4-ADC7-Pad22)") (class "Default")
      (node (ref "U4") (pin "22") (pinfunction "ADC7_22") (pintype "bidirectional"))
    )
  )
)
